# Sheet1.net
KiCad netlist of a schematic drawn in Altium Designer
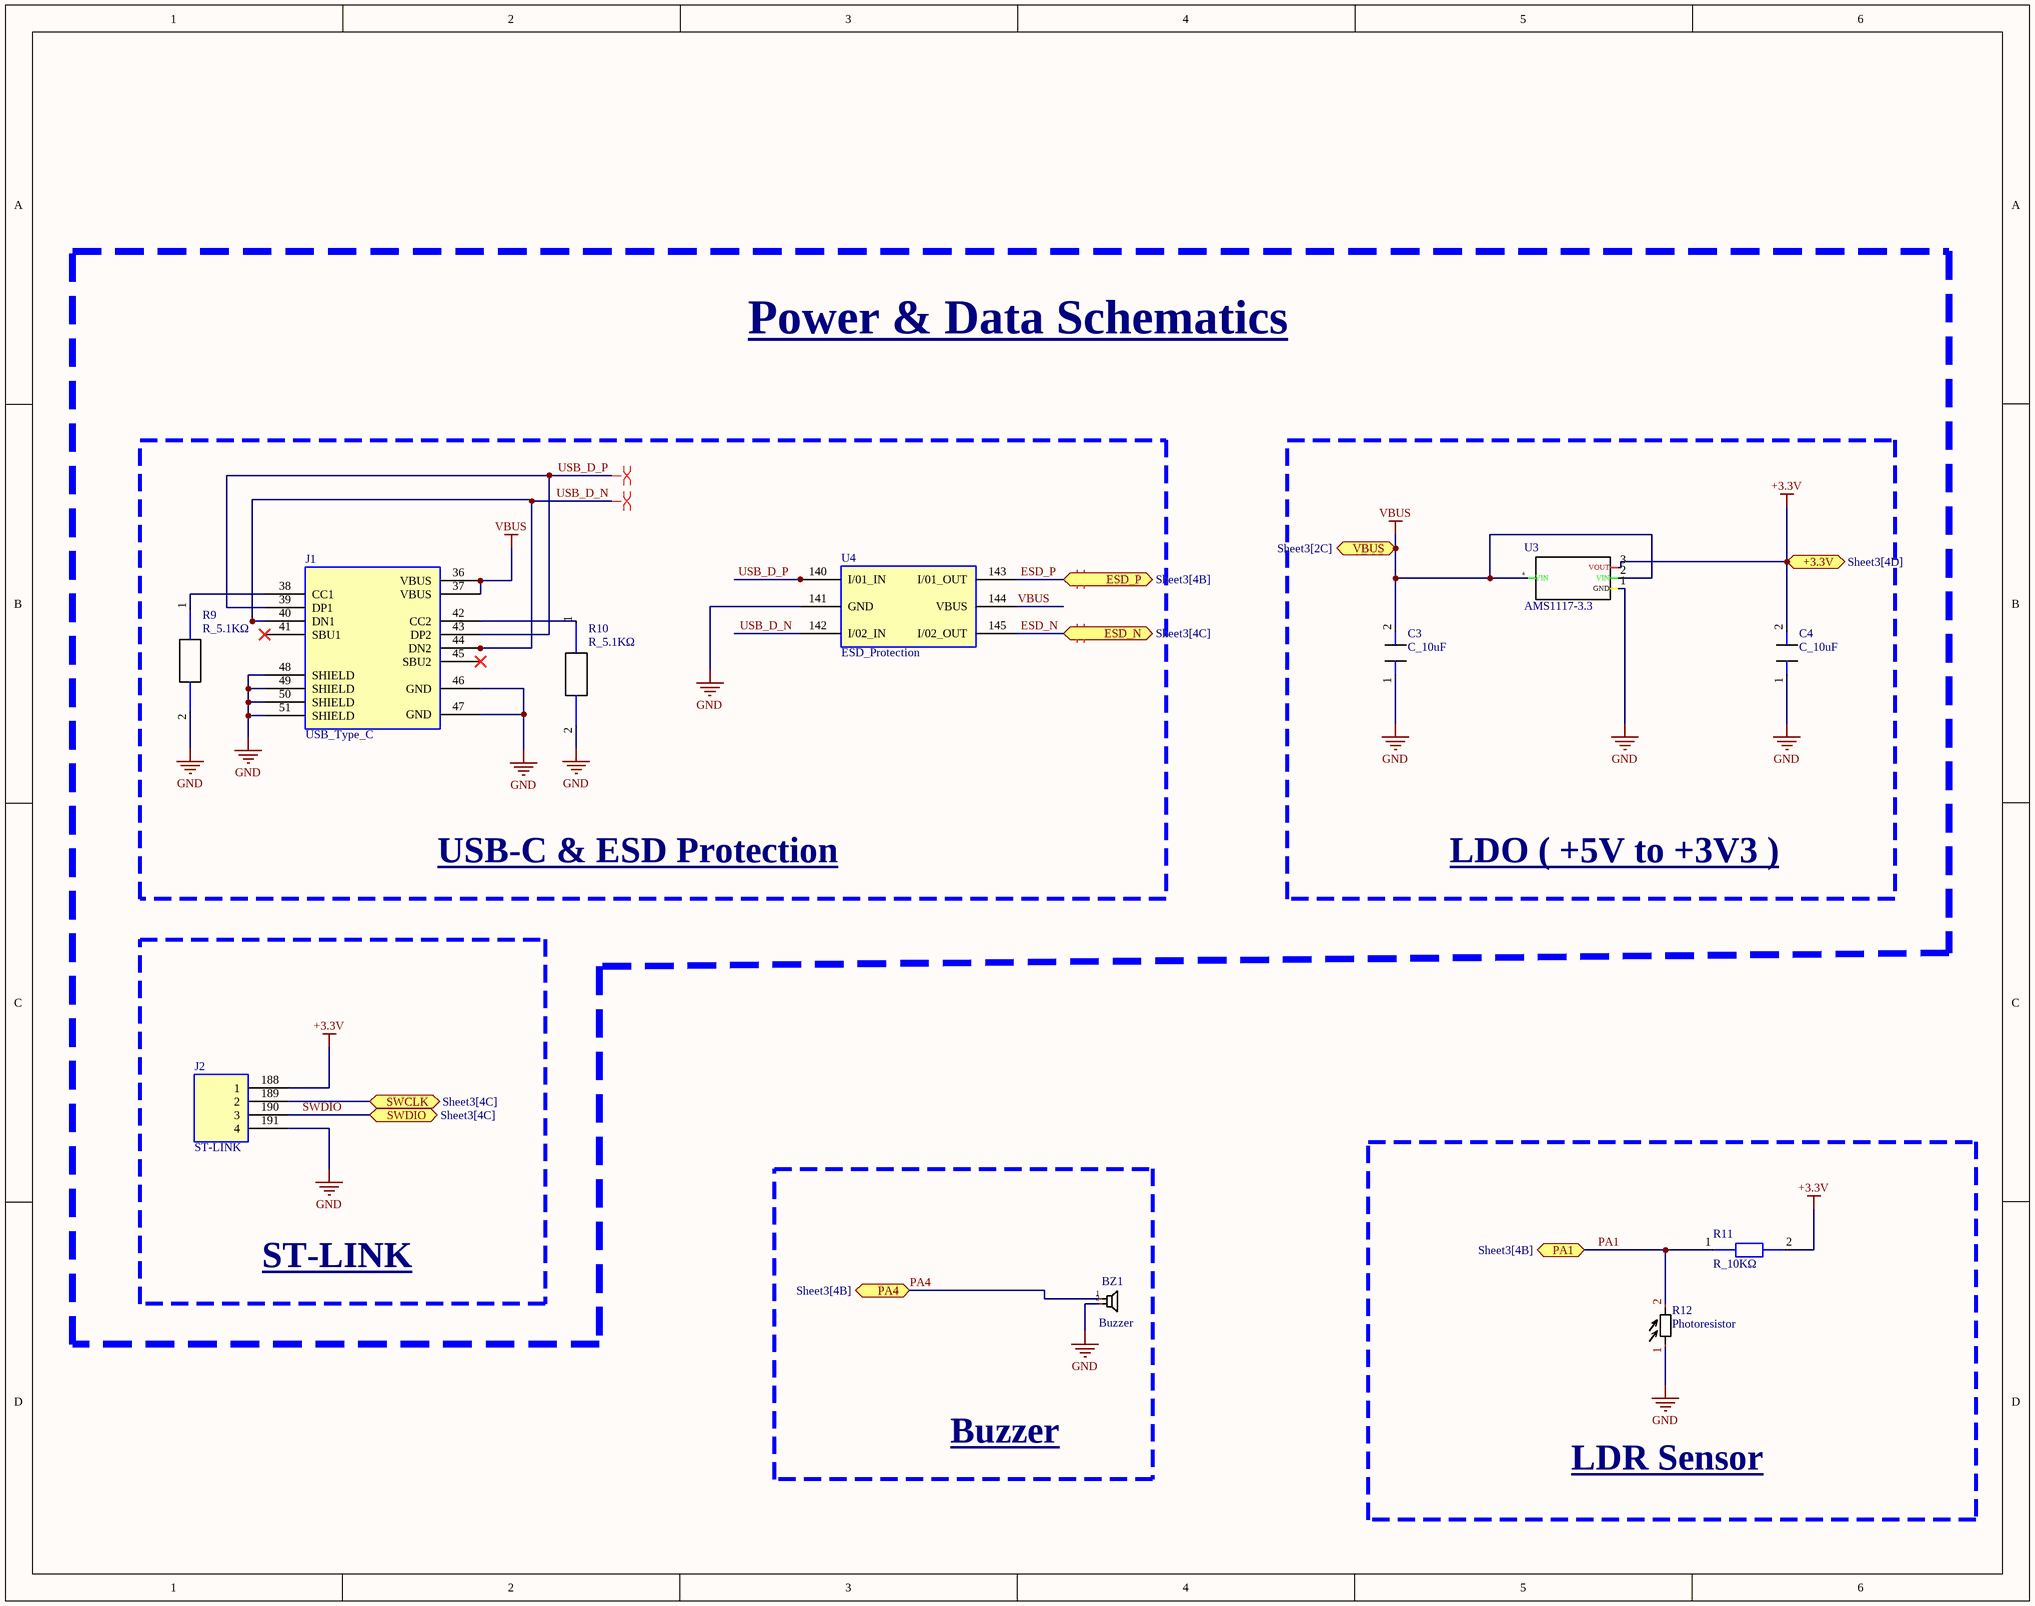
[diagram p0: Sheet1.SchDoc]

(export (version "E")
  (design (tool "Eeschema 10.0.6"))
  (components
    (comp (ref "BZ1")
      (value "Buzzer")
      (footprint "BUZZER")
      (fields (field (name "MF") "CUI"))
      (libsource (lib "Schlib3") (part "Buzzer"))
    )
    (comp (ref "C3")
      (value "C_10uF")
      (footprint "CAP_10uF")
      (description "CAP CER 10uF 25V X5R 0805")
      (fields (field (name "MFR") "Samsung Electro-Mechanics") (field (name "MFR PART #") "CL21A106KAYNNNE"))
      (libsource (lib "Schlib3") (part "C_10uF"))
    )
    (comp (ref "C4")
      (value "C_10uF")
      (footprint "CAP_10uF")
      (description "CAP CER 10uF 25V X5R 0805")
      (fields (field (name "MFR") "Samsung Electro-Mechanics") (field (name "MFR PART #") "CL21A106KAYNNNE"))
      (libsource (lib "Schlib3") (part "C_10uF"))
    )
    (comp (ref "J1")
      (value "USB_Type_C")
      (footprint "USB_TYPE_C")
      (description "CONN RCPT Type-C 16POS SMD")
      (fields (field (name "MFR") "Korean Hroparts Elec") (field (name "MFR PART #") "TYPE-C-31-M-12"))
      (libsource (lib "Schlib3") (part "USB_Type_C"))
    )
    (comp (ref "J2")
      (value "ST-LINK")
      (footprint "4_MALE_HEADER")
      (fields (field (name "MFR") "TE Connectivity") (field (name "MFR PART #") "3-641215-4"))
      (libsource (lib "Schlib3") (part "4_Male_Header"))
    )
    (comp (ref "R9")
      (value "R_5.1KΩ")
      (footprint "RES_5.1K")
      (description "RES 5.1kΩ ±1% 125mW 0805")
      (fields (field (name "MFR") "UNI-ROYAL") (field (name "MFR PART #") "0805W8F5101T5E"))
      (libsource (lib "Schlib3") (part "R_5.1KΩ"))
    )
    (comp (ref "R10")
      (value "R_5.1KΩ")
      (footprint "RES_5.1K")
      (description "RES 5.1kΩ ±1% 125mW 0805")
      (fields (field (name "MFR") "UNI-ROYAL") (field (name "MFR PART #") "0805W8F5101T5E"))
      (libsource (lib "Schlib3") (part "R_5.1KΩ"))
    )
    (comp (ref "R11")
      (value "R_10KΩ")
      (footprint "RES_10K")
      (description "RES 10kΩ ±1% 125mW 0805")
      (fields (field (name "MFR") "FOJAN") (field (name "MFR PART #") "FRC0805F1002TS"))
      (libsource (lib "Schlib3") (part "R_10KΩ"))
    )
    (comp (ref "R12")
      (value "Photoresistor")
      (footprint "PHOTORESISTOR")
      (description "540nm 5kΩ~10kΩ 500kΩ Through Hole,P=3mm Photoresistors")
      (fields (field (name "MF") "Senba Sensing Tech") (field (name "MPN") "GL5516"))
      (libsource (lib "Schlib3") (part "Photoresistor"))
    )
    (comp (ref "U3")
      (value "AMS1117-3.3")
      (footprint "AMS1117_3.3V")
      (description "1A Low Dropout (LDO) Regulator")
      (libsource (lib "Schlib3") (part "AMS1117-3.3"))
    )
    (comp (ref "U4")
      (value "ESD_Protection")
      (footprint "ESD_PROTECTION")
      (description "ESD DIODE 5.25VWM 17VC SOT-23-6L")
      (fields (field (name "MFR") "ST") (field (name "MFR PART #") "USBLC6-2SC6"))
      (libsource (lib "Schlib3") (part "ESD_Protection"))
    )
  )
  (nets
    (net (code "1") (name "+3.3V") (class "Default")
      (node (ref "C4") (pin "2") (pinfunction "2_2") (pintype "passive"))
      (node (ref "J2") (pin "188") (pinfunction "1_188") (pintype "passive"))
      (node (ref "R11") (pin "2") (pinfunction "15_2") (pintype "passive"))
      (node (ref "U3") (pin "3") (pinfunction "VOUT_3") (pintype "passive"))
    )
    (net (code "2") (name "/ESD_N") (class "Default")
      (node (ref "U4") (pin "145") (pinfunction "I/02_OUT_145") (pintype "passive"))
    )
    (net (code "3") (name "/ESD_P") (class "Default")
      (node (ref "U4") (pin "143") (pinfunction "I/01_OUT_143") (pintype "passive"))
    )
    (net (code "4") (name "/PA1") (class "Default")
      (node (ref "R11") (pin "1") (pinfunction "14_1") (pintype "passive"))
      (node (ref "R12") (pin "2") (pinfunction "2_2") (pintype "passive"))
    )
    (net (code "5") (name "/PA4") (class "Default")
      (node (ref "BZ1") (pin "1") (pinfunction "5_1") (pintype "passive"))
    )
    (net (code "6") (name "/SWCLK") (class "Default")
      (node (ref "J2") (pin "189") (pinfunction "2_189") (pintype "passive"))
    )
    (net (code "7") (name "/SWDIO") (class "Default")
      (node (ref "J2") (pin "190") (pinfunction "3_190") (pintype "passive"))
    )
    (net (code "8") (name "/USB_D_N") (class "Default")
      (node (ref "J1") (pin "40") (pinfunction "DN1_40") (pintype "passive"))
      (node (ref "J1") (pin "44") (pinfunction "DN2_44") (pintype "passive"))
      (node (ref "U4") (pin "142") (pinfunction "I/02_IN_142") (pintype "passive"))
    )
    (net (code "9") (name "/USB_D_P") (class "Default")
      (node (ref "J1") (pin "39") (pinfunction "DP1_39") (pintype "passive"))
      (node (ref "J1") (pin "43") (pinfunction "DP2_43") (pintype "passive"))
      (node (ref "U4") (pin "140") (pinfunction "I/01_IN_140") (pintype "passive"))
    )
    (net (code "10") (name "GND") (class "Default")
      (node (ref "BZ1") (pin "2") (pinfunction "6_2") (pintype "passive"))
      (node (ref "C3") (pin "1") (pinfunction "1_1") (pintype "passive"))
      (node (ref "C4") (pin "1") (pinfunction "1_1") (pintype "passive"))
      (node (ref "J1") (pin "46") (pinfunction "GND_46") (pintype "passive"))
      (node (ref "J1") (pin "47") (pinfunction "GND_47") (pintype "passive"))
      (node (ref "J1") (pin "48") (pinfunction "SHIELD_48") (pintype "passive"))
      (node (ref "J1") (pin "49") (pinfunction "SHIELD_49") (pintype "passive"))
      (node (ref "J1") (pin "50") (pinfunction "SHIELD_50") (pintype "passive"))
      (node (ref "J1") (pin "51") (pinfunction "SHIELD_51") (pintype "passive"))
      (node (ref "J2") (pin "191") (pinfunction "4_191") (pintype "passive"))
      (node (ref "R10") (pin "2") (pinfunction "15_2") (pintype "passive"))
      (node (ref "R12") (pin "1") (pinfunction "1_1") (pintype "passive"))
      (node (ref "R9") (pin "2") (pinfunction "15_2") (pintype "passive"))
      (node (ref "U3") (pin "1") (pinfunction "GND_1") (pintype "passive"))
      (node (ref "U4") (pin "141") (pinfunction "GND_141") (pintype "passive"))
    )
    (net (code "11") (name "Net-(J1-CC1)") (class "Default")
      (node (ref "J1") (pin "38") (pinfunction "CC1_38") (pintype "passive"))
      (node (ref "R9") (pin "1") (pinfunction "14_1") (pintype "passive"))
    )
    (net (code "12") (name "Net-(J1-CC2)") (class "Default")
      (node (ref "J1") (pin "42") (pinfunction "CC2_42") (pintype "passive"))
      (node (ref "R10") (pin "1") (pinfunction "14_1") (pintype "passive"))
    )
    (net (code "13") (name "VBUS") (class "Default")
      (node (ref "C3") (pin "2") (pinfunction "2_2") (pintype "passive"))
      (node (ref "J1") (pin "36") (pinfunction "VBUS_36") (pintype "passive"))
      (node (ref "J1") (pin "37") (pinfunction "VBUS_37") (pintype "passive"))
      (node (ref "U3") (pin "2") (pinfunction "VIN_2") (pintype "passive"))
      (node (ref "U3") (pin "4") (pinfunction "VIN_4") (pintype "passive"))
      (node (ref "U4") (pin "144") (pinfunction "VBUS_144") (pintype "passive"))
    )
    (net (code "14") (name "unconnected-(J1-SBU1-Pad41)") (class "Default")
      (node (ref "J1") (pin "41") (pinfunction "SBU1_41") (pintype "passive+no_connect"))
    )
    (net (code "15") (name "unconnected-(J1-SBU2-Pad45)") (class "Default")
      (node (ref "J1") (pin "45") (pinfunction "SBU2_45") (pintype "passive+no_connect"))
    )
  )
)
